# 6_Channels_RX_V1_Schematic.net
KiCad netlist of a schematic drawn in Altium Designer
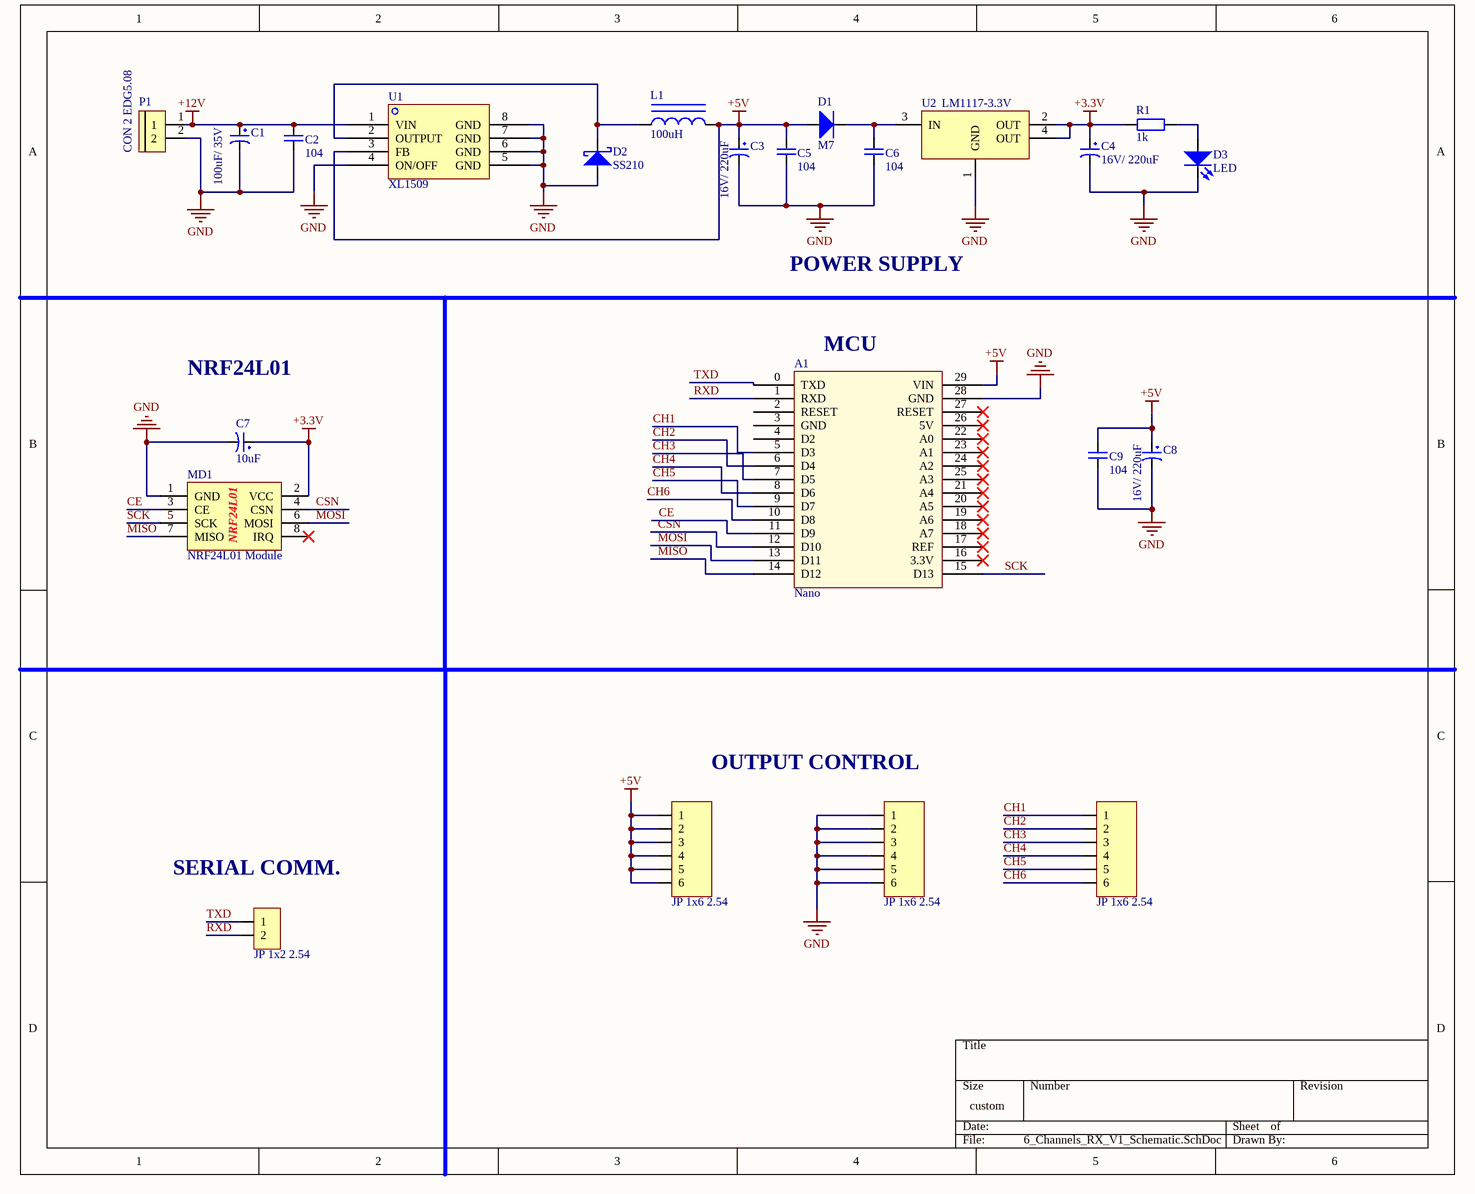
[diagram p0: 6_Channels_RX_V1_Schematic.SchDoc]

(export (version "E")
  (design (tool "Eeschema 10.0.6"))
  (components
    (comp (ref "A1")
      (value "Nano")
      (footprint "Arduino nano")
      (libsource (lib "Altium_Lib_by_KhueNguyenCreator") (part "Arduino Nano"))
    )
    (comp (ref "C1")
      (value "100uF/ 35V")
      (footprint "CAP SMD ALUMINUM D8")
      (libsource (lib "Electronic4u") (part "Cap_Polar"))
    )
    (comp (ref "C2")
      (value "104")
      (footprint "SM-0805")
      (libsource (lib "Electronic4u") (part "Cap_Non-Polar"))
    )
    (comp (ref "C3")
      (value "16V/ 220uF")
      (footprint "CAP SMD ALUMINUM D8")
      (libsource (lib "Electronic4u") (part "Cap_Polar"))
    )
    (comp (ref "C4")
      (value "16V/ 220uF")
      (footprint "CAP SMD ALUMINUM D8")
      (libsource (lib "Electronic4u") (part "Cap_Polar"))
    )
    (comp (ref "C5")
      (value "104")
      (footprint "SM-0805")
      (libsource (lib "Electronic4u") (part "Cap_Non-Polar"))
    )
    (comp (ref "C6")
      (value "104")
      (footprint "SM-0805")
      (libsource (lib "Electronic4u") (part "Cap_Non-Polar"))
    )
    (comp (ref "C7")
      (value "10uF")
      (footprint "tu hoa 8mm")
      (description "Cắm")
      (libsource (lib "Altium_Lib_by_KhueNguyenCreator") (part "Tu Hoa 100uF 35V 8x11"))
    )
    (comp (ref "C8")
      (value "16V/ 220uF")
      (footprint "CAP SMD ALUMINUM D8")
      (libsource (lib "Electronic4u") (part "Cap_Polar"))
    )
    (comp (ref "C9")
      (value "104")
      (footprint "SM-0805")
      (libsource (lib "Electronic4u") (part "Cap_Non-Polar"))
    )
    (comp (ref "D1")
      (value "M7")
      (footprint "DO-214AC")
      (description "Diode Standard")
      (fields (field (name "PART NUMBER") "LED 3 ly Single Colour"))
      (libsource (lib "Electronic4u") (part "Diode Standard"))
    )
    (comp (ref "D2")
      (value "SS210")
      (footprint "DO-214AC")
      (description "Diode Schottky")
      (fields (field (name "PART NUMBER") "LED 3 ly Single Colour"))
      (libsource (lib "Electronic4u") (part "Diode Schottky"))
    )
    (comp (ref "D3")
      (value "LED")
      (footprint "LED-3MM GRE")
      (description "LED Single")
      (libsource (lib "Electronic4u") (part "LED"))
    )
    (comp (ref "JP1")
      (value "JP 1x6 2.54")
      (footprint "JP 1x6 DT")
      (description "Cắm")
      (libsource (lib "Altium_Lib_by_KhueNguyenCreator") (part "JP 1x6 2.54 Duc Thang"))
    )
    (comp (ref "JP2")
      (value "JP 1x6 2.54")
      (footprint "JP 1x6 DT")
      (description "Cắm")
      (libsource (lib "Altium_Lib_by_KhueNguyenCreator") (part "JP 1x6 2.54 Duc Thang"))
    )
    (comp (ref "JP3")
      (value "JP 1x6 2.54")
      (footprint "JP 1x6 DT")
      (description "Cắm")
      (libsource (lib "Altium_Lib_by_KhueNguyenCreator") (part "JP 1x6 2.54 Duc Thang"))
    )
    (comp (ref "JP4")
      (value "JP 1x2 2.54")
      (footprint "JP 1x2 DT")
      (description "Cắm")
      (libsource (lib "Altium_Lib_by_KhueNguyenCreator") (part "JP 1x2 2.54 Duc Thang"))
    )
    (comp (ref "L1")
      (value "100uH")
      (footprint "INDUCTOR SMD 7342 7.3X7.3X4.2mm")
      (description "Magnetic-Core Inductor")
      (libsource (lib "Electronic4u") (part "Inductor Iron"))
    )
    (comp (ref "MD1")
      (value "NRF24L01 Module")
      (footprint "NRF24L01")
      (libsource (lib "Altium_Lib_by_KhueNguyenCreator") (part "NRF24L01 Module"))
    )
    (comp (ref "P1")
      (value "CON 2 EDG5.08")
      (footprint "CON 2 2EDG5.08")
      (description "Cắm")
      (libsource (lib "Altium_Lib_by_KhueNguyenCreator") (part "CON 2 EDG5.08"))
    )
    (comp (ref "R1")
      (value "1k")
      (footprint "RESISTOR SMD 0805")
      (libsource (lib "Electronic4u") (part "Resistor"))
    )
    (comp (ref "U1")
      (value "XL1509")
      (footprint "SOP8")
      (description "IC power sop8")
      (libsource (lib "FMS_PcbLib1") (part "XL1509"))
    )
    (comp (ref "U2")
      (value "LM1117-3.3V")
      (footprint "SOT223-4N")
      (description "800mA Low-Dropout Linear Regulator")
      (fields (field (name "CREATOR") "Nguyen Ba Bien"))
      (libsource (lib "Electronic4u") (part "LM1117"))
    )
  )
  (nets
    (net (code "1") (name "+3.3V") (class "Default")
      (node (ref "C4") (pin "1") (pinfunction "1_1") (pintype "passive"))
      (node (ref "C7") (pin "1") (pinfunction "1_1") (pintype "passive"))
      (node (ref "MD1") (pin "2") (pinfunction "VCC_2") (pintype "passive"))
      (node (ref "R1") (pin "1") (pinfunction "1_1") (pintype "passive"))
      (node (ref "U2") (pin "2") (pinfunction "OUT_2") (pintype "passive"))
      (node (ref "U2") (pin "4") (pinfunction "OUT_4") (pintype "passive"))
    )
    (net (code "2") (name "+5V") (class "Default")
      (node (ref "A1") (pin "29") (pinfunction "VIN_29") (pintype "passive"))
      (node (ref "C3") (pin "1") (pinfunction "1_1") (pintype "passive"))
      (node (ref "C5") (pin "2") (pinfunction "2_2") (pintype "passive"))
      (node (ref "C8") (pin "1") (pinfunction "1_1") (pintype "passive"))
      (node (ref "C9") (pin "2") (pinfunction "2_2") (pintype "passive"))
      (node (ref "D1") (pin "1") (pinfunction "1_1") (pintype "passive"))
      (node (ref "JP1") (pin "1") (pinfunction "1_1") (pintype "passive"))
      (node (ref "JP1") (pin "2") (pinfunction "2_2") (pintype "passive"))
      (node (ref "JP1") (pin "3") (pinfunction "3_3") (pintype "passive"))
      (node (ref "JP1") (pin "4") (pinfunction "4_4") (pintype "passive"))
      (node (ref "JP1") (pin "5") (pinfunction "5_5") (pintype "passive"))
      (node (ref "JP1") (pin "6") (pinfunction "6_6") (pintype "passive"))
      (node (ref "L1") (pin "2") (pinfunction "2_2") (pintype "passive"))
      (node (ref "U1") (pin "3") (pinfunction "FB_3") (pintype "passive"))
    )
    (net (code "3") (name "+12V") (class "Default")
      (node (ref "C1") (pin "1") (pinfunction "1_1") (pintype "passive"))
      (node (ref "C2") (pin "2") (pinfunction "2_2") (pintype "passive"))
      (node (ref "P1") (pin "1") (pinfunction "1_1") (pintype "passive"))
      (node (ref "U1") (pin "1") (pinfunction "VIN_1") (pintype "passive"))
    )
    (net (code "4") (name "/CE") (class "Default")
      (node (ref "A1") (pin "11") (pinfunction "D9_11") (pintype "passive"))
      (node (ref "MD1") (pin "3") (pinfunction "CE_3") (pintype "passive"))
    )
    (net (code "5") (name "/CH1") (class "Default")
      (node (ref "A1") (pin "5") (pinfunction "D3_5") (pintype "passive"))
      (node (ref "JP3") (pin "1") (pinfunction "1_1") (pintype "passive"))
    )
    (net (code "6") (name "/CH2") (class "Default")
      (node (ref "A1") (pin "6") (pinfunction "D4_6") (pintype "passive"))
      (node (ref "JP3") (pin "2") (pinfunction "2_2") (pintype "passive"))
    )
    (net (code "7") (name "/CH3") (class "Default")
      (node (ref "A1") (pin "7") (pinfunction "D5_7") (pintype "passive"))
      (node (ref "JP3") (pin "3") (pinfunction "3_3") (pintype "passive"))
    )
    (net (code "8") (name "/CH4") (class "Default")
      (node (ref "A1") (pin "8") (pinfunction "D6_8") (pintype "passive"))
      (node (ref "JP3") (pin "4") (pinfunction "4_4") (pintype "passive"))
    )
    (net (code "9") (name "/CH5") (class "Default")
      (node (ref "A1") (pin "9") (pinfunction "D7_9") (pintype "passive"))
      (node (ref "JP3") (pin "5") (pinfunction "5_5") (pintype "passive"))
    )
    (net (code "10") (name "/CH6") (class "Default")
      (node (ref "A1") (pin "10") (pinfunction "D8_10") (pintype "passive"))
      (node (ref "JP3") (pin "6") (pinfunction "6_6") (pintype "passive"))
    )
    (net (code "11") (name "/CSN") (class "Default")
      (node (ref "A1") (pin "12") (pinfunction "D10_12") (pintype "passive"))
      (node (ref "MD1") (pin "4") (pinfunction "CSN_4") (pintype "passive"))
    )
    (net (code "12") (name "/MISO") (class "Default")
      (node (ref "A1") (pin "14") (pinfunction "D12_14") (pintype "passive"))
      (node (ref "MD1") (pin "7") (pinfunction "MISO_7") (pintype "passive"))
    )
    (net (code "13") (name "/MOSI") (class "Default")
      (node (ref "A1") (pin "13") (pinfunction "D11_13") (pintype "passive"))
      (node (ref "MD1") (pin "6") (pinfunction "MOSI_6") (pintype "passive"))
    )
    (net (code "14") (name "/RXD") (class "Default")
      (node (ref "A1") (pin "1") (pinfunction "RXD_1") (pintype "passive"))
      (node (ref "JP4") (pin "2") (pinfunction "2_2") (pintype "passive"))
    )
    (net (code "15") (name "/SCK") (class "Default")
      (node (ref "A1") (pin "15") (pinfunction "D13_15") (pintype "passive"))
      (node (ref "MD1") (pin "5") (pinfunction "SCK_5") (pintype "passive"))
    )
    (net (code "16") (name "/TXD") (class "Default")
      (node (ref "A1") (pin "0") (pinfunction "TXD_0") (pintype "passive"))
      (node (ref "JP4") (pin "1") (pinfunction "1_1") (pintype "passive"))
    )
    (net (code "17") (name "GND") (class "Default")
      (node (ref "A1") (pin "28") (pinfunction "GND_28") (pintype "passive"))
      (node (ref "C1") (pin "2") (pinfunction "2_2") (pintype "passive"))
      (node (ref "C2") (pin "1") (pinfunction "1_1") (pintype "passive"))
      (node (ref "C3") (pin "2") (pinfunction "2_2") (pintype "passive"))
      (node (ref "C4") (pin "2") (pinfunction "2_2") (pintype "passive"))
      (node (ref "C5") (pin "1") (pinfunction "1_1") (pintype "passive"))
      (node (ref "C6") (pin "1") (pinfunction "1_1") (pintype "passive"))
      (node (ref "C7") (pin "2") (pinfunction "2_2") (pintype "passive"))
      (node (ref "C8") (pin "2") (pinfunction "2_2") (pintype "passive"))
      (node (ref "C9") (pin "1") (pinfunction "1_1") (pintype "passive"))
      (node (ref "D2") (pin "1") (pinfunction "1_1") (pintype "passive"))
      (node (ref "D3") (pin "2") (pinfunction "2_2") (pintype "passive"))
      (node (ref "JP2") (pin "1") (pinfunction "1_1") (pintype "passive"))
      (node (ref "JP2") (pin "2") (pinfunction "2_2") (pintype "passive"))
      (node (ref "JP2") (pin "3") (pinfunction "3_3") (pintype "passive"))
      (node (ref "JP2") (pin "4") (pinfunction "4_4") (pintype "passive"))
      (node (ref "JP2") (pin "5") (pinfunction "5_5") (pintype "passive"))
      (node (ref "JP2") (pin "6") (pinfunction "6_6") (pintype "passive"))
      (node (ref "MD1") (pin "1") (pinfunction "GND_1") (pintype "passive"))
      (node (ref "P1") (pin "2") (pinfunction "2_2") (pintype "passive"))
      (node (ref "U1") (pin "4") (pinfunction "ON/OFF_4") (pintype "passive"))
      (node (ref "U1") (pin "5") (pinfunction "GND_5") (pintype "passive"))
      (node (ref "U1") (pin "6") (pinfunction "GND_6") (pintype "passive"))
      (node (ref "U1") (pin "7") (pinfunction "GND_7") (pintype "passive"))
      (node (ref "U1") (pin "8") (pinfunction "GND_8") (pintype "passive"))
      (node (ref "U2") (pin "1") (pinfunction "GND_1") (pintype "passive"))
    )
    (net (code "18") (name "Net-(D3-Pad1)") (class "Default")
      (node (ref "D3") (pin "1") (pinfunction "1_1") (pintype "passive"))
      (node (ref "R1") (pin "2") (pinfunction "2_2") (pintype "passive"))
    )
    (net (code "19") (name "Net-(U1-OUTPUT)") (class "Default")
      (node (ref "D2") (pin "2") (pinfunction "2_2") (pintype "passive"))
      (node (ref "L1") (pin "1") (pinfunction "1_1") (pintype "passive"))
      (node (ref "U1") (pin "2") (pinfunction "OUTPUT_2") (pintype "passive"))
    )
    (net (code "20") (name "Net-(U2-IN)") (class "Default")
      (node (ref "C6") (pin "2") (pinfunction "2_2") (pintype "passive"))
      (node (ref "D1") (pin "2") (pinfunction "2_2") (pintype "passive"))
      (node (ref "U2") (pin "3") (pinfunction "IN_3") (pintype "passive"))
    )
    (net (code "21") (name "unconnected-(A1-3.3V-Pad16)") (class "Default")
      (node (ref "A1") (pin "16") (pinfunction "3.3V_16") (pintype "passive+no_connect"))
    )
    (net (code "22") (name "unconnected-(A1-5V-Pad26)") (class "Default")
      (node (ref "A1") (pin "26") (pinfunction "5V_26") (pintype "passive+no_connect"))
    )
    (net (code "23") (name "unconnected-(A1-A0-Pad22)") (class "Default")
      (node (ref "A1") (pin "22") (pinfunction "A0_22") (pintype "passive+no_connect"))
    )
    (net (code "24") (name "unconnected-(A1-A1-Pad23)") (class "Default")
      (node (ref "A1") (pin "23") (pinfunction "A1_23") (pintype "passive+no_connect"))
    )
    (net (code "25") (name "unconnected-(A1-A2-Pad24)") (class "Default")
      (node (ref "A1") (pin "24") (pinfunction "A2_24") (pintype "passive+no_connect"))
    )
    (net (code "26") (name "unconnected-(A1-A3-Pad25)") (class "Default")
      (node (ref "A1") (pin "25") (pinfunction "A3_25") (pintype "passive+no_connect"))
    )
    (net (code "27") (name "unconnected-(A1-A4-Pad21)") (class "Default")
      (node (ref "A1") (pin "21") (pinfunction "A4_21") (pintype "passive+no_connect"))
    )
    (net (code "28") (name "unconnected-(A1-A5-Pad20)") (class "Default")
      (node (ref "A1") (pin "20") (pinfunction "A5_20") (pintype "passive+no_connect"))
    )
    (net (code "29") (name "unconnected-(A1-A6-Pad19)") (class "Default")
      (node (ref "A1") (pin "19") (pinfunction "A6_19") (pintype "passive+no_connect"))
    )
    (net (code "30") (name "unconnected-(A1-A7-Pad18)") (class "Default")
      (node (ref "A1") (pin "18") (pinfunction "A7_18") (pintype "passive+no_connect"))
    )
    (net (code "31") (name "unconnected-(A1-D2-Pad4)") (class "Default")
      (node (ref "A1") (pin "4") (pinfunction "D2_4") (pintype "passive"))
    )
    (net (code "32") (name "unconnected-(A1-GND-Pad3)") (class "Default")
      (node (ref "A1") (pin "3") (pinfunction "GND_3") (pintype "passive"))
    )
    (net (code "33") (name "unconnected-(A1-REF-Pad17)") (class "Default")
      (node (ref "A1") (pin "17") (pinfunction "REF_17") (pintype "passive+no_connect"))
    )
    (net (code "34") (name "unconnected-(A1-RESET-Pad2)") (class "Default")
      (node (ref "A1") (pin "2") (pinfunction "RESET_2") (pintype "passive"))
    )
    (net (code "35") (name "unconnected-(A1-RESET-Pad27)") (class "Default")
      (node (ref "A1") (pin "27") (pinfunction "RESET_27") (pintype "passive+no_connect"))
    )
    (net (code "36") (name "unconnected-(MD1-IRQ-Pad8)") (class "Default")
      (node (ref "MD1") (pin "8") (pinfunction "IRQ_8") (pintype "passive+no_connect"))
    )
  )
)
